# 8-AUDIO.net
KiCad netlist of a schematic drawn in Altium Designer
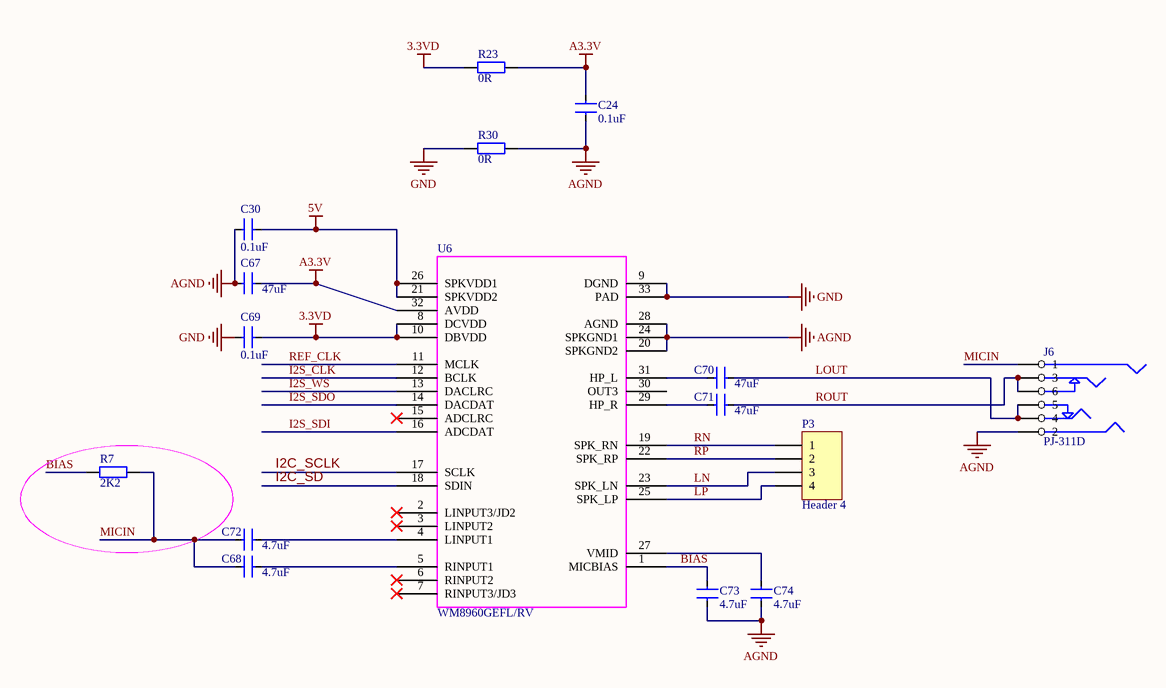
[diagram p0: 8-AUDIO.SchDoc]

(export (version "E")
  (design (tool "Eeschema 10.0.6"))
  (components
    (comp (ref "C24")
      (value "0.1uF")
      (footprint "C0402")
      (description "普通小电容")
      (libsource (lib "LIB_MANGO") (part "CAP"))
    )
    (comp (ref "C30")
      (value "0.1uF")
      (footprint "C0402")
      (description "普通小电容")
      (libsource (lib "LIB_MANGO") (part "CAP"))
    )
    (comp (ref "C67")
      (value "47uF")
      (footprint "0805C")
      (description "普通小电容")
      (libsource (lib "LIB_MANGO") (part "CAP"))
    )
    (comp (ref "C68")
      (value "4.7uF")
      (footprint "C0402")
      (description "普通小电容")
      (libsource (lib "LIB_MANGO") (part "CAP"))
    )
    (comp (ref "C69")
      (value "0.1uF")
      (footprint "C0402")
      (description "普通小电容")
      (libsource (lib "LIB_MANGO") (part "CAP"))
    )
    (comp (ref "C70")
      (value "47uF")
      (footprint "0805C")
      (description "普通小电容")
      (libsource (lib "LIB_MANGO") (part "CAP"))
    )
    (comp (ref "C71")
      (value "47uF")
      (footprint "0805C")
      (description "普通小电容")
      (libsource (lib "LIB_MANGO") (part "CAP"))
    )
    (comp (ref "C72")
      (value "4.7uF")
      (footprint "C0402")
      (description "普通小电容")
      (libsource (lib "LIB_MANGO") (part "CAP"))
    )
    (comp (ref "C73")
      (value "4.7uF")
      (footprint "C0402")
      (description "普通小电容")
      (libsource (lib "LIB_MANGO") (part "CAP"))
    )
    (comp (ref "C74")
      (value "4.7uF")
      (footprint "C0402")
      (description "普通小电容")
      (libsource (lib "LIB_MANGO") (part "CAP"))
    )
    (comp (ref "J6") (value "PJ-311D") (footprint "PJ311D") (libsource (lib "LIB_MANGO") (part "PJ-311D")))
    (comp (ref "P3")
      (value "Header 4")
      (footprint "HDR1X4 -2.0")
      (description "Header, 4-Pin")
      (fields (field (name "PUBLISHER") "Altium Limited"))
      (libsource (lib "LIB_MANGO") (part "Header 4"))
    )
    (comp (ref "R7")
      (value "2K2")
      (footprint "R0402")
      (description "普通电阻")
      (libsource (lib "LIB_MANGO") (part "RES"))
    )
    (comp (ref "R23")
      (value "0R")
      (footprint "R0402")
      (description "普通电阻")
      (libsource (lib "LIB_MANGO") (part "RES"))
    )
    (comp (ref "R30")
      (value "0R")
      (footprint "R0402")
      (description "普通电阻")
      (libsource (lib "LIB_MANGO") (part "RES"))
    )
    (comp (ref "U6")
      (value "WM8960GEFL/RV")
      (footprint "QFN50P500X500X100-33N")
      (libsource (lib "ALL") (part "WM8960GEFL/RV"))
    )
  )
  (nets
    (net (code "1") (name "/BIAS") (class "Default")
      (node (ref "C73") (pin "2") (pinfunction "2_2") (pintype "passive"))
      (node (ref "R7") (pin "1") (pinfunction "1_1") (pintype "passive"))
      (node (ref "U6") (pin "1") (pinfunction "MICBIAS_1") (pintype "passive"))
    )
    (net (code "2") (name "/I2C_SCLK") (class "Default")
      (node (ref "U6") (pin "17") (pinfunction "SCLK_17") (pintype "passive"))
    )
    (net (code "3") (name "/I2C_SD") (class "Default")
      (node (ref "U6") (pin "18") (pinfunction "SDIN_18") (pintype "passive"))
    )
    (net (code "4") (name "/I2S_CLK") (class "Default")
      (node (ref "U6") (pin "12") (pinfunction "BCLK_12") (pintype "passive"))
    )
    (net (code "5") (name "/I2S_SDI") (class "Default")
      (node (ref "U6") (pin "16") (pinfunction "ADCDAT_16") (pintype "passive"))
    )
    (net (code "6") (name "/I2S_SDO") (class "Default")
      (node (ref "U6") (pin "14") (pinfunction "DACDAT_14") (pintype "passive"))
    )
    (net (code "7") (name "/I2S_WS") (class "Default")
      (node (ref "U6") (pin "13") (pinfunction "DACLRC_13") (pintype "passive"))
    )
    (net (code "8") (name "/LN") (class "Default")
      (node (ref "P3") (pin "3") (pinfunction "3_3") (pintype "passive"))
      (node (ref "U6") (pin "23") (pinfunction "SPK_LN_23") (pintype "passive"))
    )
    (net (code "9") (name "/LOUT") (class "Default")
      (node (ref "C70") (pin "1") (pinfunction "1_1") (pintype "passive"))
      (node (ref "J6") (pin "4") (pinfunction "4_4") (pintype "passive"))
      (node (ref "J6") (pin "5") (pinfunction "5_5") (pintype "passive"))
    )
    (net (code "10") (name "/LP") (class "Default")
      (node (ref "P3") (pin "4") (pinfunction "4_4") (pintype "passive"))
      (node (ref "U6") (pin "25") (pinfunction "SPK_LP_25") (pintype "passive"))
    )
    (net (code "11") (name "/MICIN") (class "Default")
      (node (ref "C68") (pin "2") (pinfunction "2_2") (pintype "passive"))
      (node (ref "C72") (pin "2") (pinfunction "2_2") (pintype "passive"))
      (node (ref "J6") (pin "1") (pinfunction "1_1") (pintype "passive"))
      (node (ref "R7") (pin "2") (pinfunction "2_2") (pintype "passive"))
    )
    (net (code "12") (name "/REF_CLK") (class "Default")
      (node (ref "U6") (pin "11") (pinfunction "MCLK_11") (pintype "passive"))
    )
    (net (code "13") (name "/RN") (class "Default")
      (node (ref "P3") (pin "1") (pinfunction "1_1") (pintype "passive"))
      (node (ref "U6") (pin "19") (pinfunction "SPK_RN_19") (pintype "passive"))
    )
    (net (code "14") (name "/ROUT") (class "Default")
      (node (ref "C71") (pin "1") (pinfunction "1_1") (pintype "passive"))
      (node (ref "J6") (pin "3") (pinfunction "3_3") (pintype "passive"))
      (node (ref "J6") (pin "6") (pinfunction "6_6") (pintype "passive"))
    )
    (net (code "15") (name "/RP") (class "Default")
      (node (ref "P3") (pin "2") (pinfunction "2_2") (pintype "passive"))
      (node (ref "U6") (pin "22") (pinfunction "SPK_RP_22") (pintype "passive"))
    )
    (net (code "16") (name "3.3VD") (class "Default")
      (node (ref "C69") (pin "2") (pinfunction "2_2") (pintype "passive"))
      (node (ref "R23") (pin "1") (pinfunction "1_1") (pintype "passive"))
      (node (ref "U6") (pin "10") (pinfunction "DBVDD_10") (pintype "passive"))
      (node (ref "U6") (pin "8") (pinfunction "DCVDD_8") (pintype "passive"))
    )
    (net (code "17") (name "5V") (class "Default")
      (node (ref "C30") (pin "1") (pinfunction "1_1") (pintype "passive"))
      (node (ref "U6") (pin "21") (pinfunction "SPKVDD2_21") (pintype "passive"))
      (node (ref "U6") (pin "26") (pinfunction "SPKVDD1_26") (pintype "passive"))
    )
    (net (code "18") (name "A3.3V") (class "Default")
      (node (ref "C24") (pin "2") (pinfunction "2_2") (pintype "passive"))
      (node (ref "C67") (pin "2") (pinfunction "2_2") (pintype "passive"))
      (node (ref "R23") (pin "2") (pinfunction "2_2") (pintype "passive"))
      (node (ref "U6") (pin "32") (pinfunction "AVDD_32") (pintype "passive"))
    )
    (net (code "19") (name "AGND") (class "Default")
      (node (ref "C24") (pin "1") (pinfunction "1_1") (pintype "passive"))
      (node (ref "C30") (pin "2") (pinfunction "2_2") (pintype "passive"))
      (node (ref "C67") (pin "1") (pinfunction "1_1") (pintype "passive"))
      (node (ref "C73") (pin "1") (pinfunction "1_1") (pintype "passive"))
      (node (ref "C74") (pin "1") (pinfunction "1_1") (pintype "passive"))
      (node (ref "J6") (pin "2") (pinfunction "2_2") (pintype "passive"))
      (node (ref "R30") (pin "2") (pinfunction "2_2") (pintype "passive"))
      (node (ref "U6") (pin "20") (pinfunction "SPKGND2_20") (pintype "passive"))
      (node (ref "U6") (pin "24") (pinfunction "SPKGND1_24") (pintype "passive"))
      (node (ref "U6") (pin "28") (pinfunction "AGND_28") (pintype "passive"))
    )
    (net (code "20") (name "GND") (class "Default")
      (node (ref "C69") (pin "1") (pinfunction "1_1") (pintype "passive"))
      (node (ref "R30") (pin "1") (pinfunction "1_1") (pintype "passive"))
      (node (ref "U6") (pin "33") (pinfunction "PAD_33") (pintype "passive"))
      (node (ref "U6") (pin "9") (pinfunction "DGND_9") (pintype "passive"))
    )
    (net (code "21") (name "Net-(U6-HP_L)") (class "Default")
      (node (ref "C70") (pin "2") (pinfunction "2_2") (pintype "passive"))
      (node (ref "U6") (pin "31") (pinfunction "HP_L_31") (pintype "passive"))
    )
    (net (code "22") (name "Net-(U6-HP_R)") (class "Default")
      (node (ref "C71") (pin "2") (pinfunction "2_2") (pintype "passive"))
      (node (ref "U6") (pin "29") (pinfunction "HP_R_29") (pintype "passive"))
    )
    (net (code "23") (name "Net-(U6-LINPUT1)") (class "Default")
      (node (ref "C72") (pin "1") (pinfunction "1_1") (pintype "passive"))
      (node (ref "U6") (pin "4") (pinfunction "LINPUT1_4") (pintype "passive"))
    )
    (net (code "24") (name "Net-(U6-RINPUT1)") (class "Default")
      (node (ref "C68") (pin "1") (pinfunction "1_1") (pintype "passive"))
      (node (ref "U6") (pin "5") (pinfunction "RINPUT1_5") (pintype "passive"))
    )
    (net (code "25") (name "Net-(U6-VMID)") (class "Default")
      (node (ref "C74") (pin "2") (pinfunction "2_2") (pintype "passive"))
      (node (ref "U6") (pin "27") (pinfunction "VMID_27") (pintype "passive"))
    )
    (net (code "26") (name "unconnected-(U6-ADCLRC-Pad15)") (class "Default")
      (node (ref "U6") (pin "15") (pinfunction "ADCLRC_15") (pintype "passive+no_connect"))
    )
    (net (code "27") (name "unconnected-(U6-LINPUT2-Pad3)") (class "Default")
      (node (ref "U6") (pin "3") (pinfunction "LINPUT2_3") (pintype "passive+no_connect"))
    )
    (net (code "28") (name "unconnected-(U6-LINPUT3{slash}JD2-Pad2)") (class "Default")
      (node (ref "U6") (pin "2") (pinfunction "LINPUT3/JD2_2") (pintype "passive+no_connect"))
    )
    (net (code "29") (name "unconnected-(U6-OUT3-Pad30)") (class "Default")
      (node (ref "U6") (pin "30") (pinfunction "OUT3_30") (pintype "passive"))
    )
    (net (code "30") (name "unconnected-(U6-RINPUT2-Pad6)") (class "Default")
      (node (ref "U6") (pin "6") (pinfunction "RINPUT2_6") (pintype "passive+no_connect"))
    )
    (net (code "31") (name "unconnected-(U6-RINPUT3{slash}JD3-Pad7)") (class "Default")
      (node (ref "U6") (pin "7") (pinfunction "RINPUT3/JD3_7") (pintype "passive+no_connect"))
    )
  )
)
